# neonpixelbar.net
KiCad netlist of a schematic drawn in EAGLE
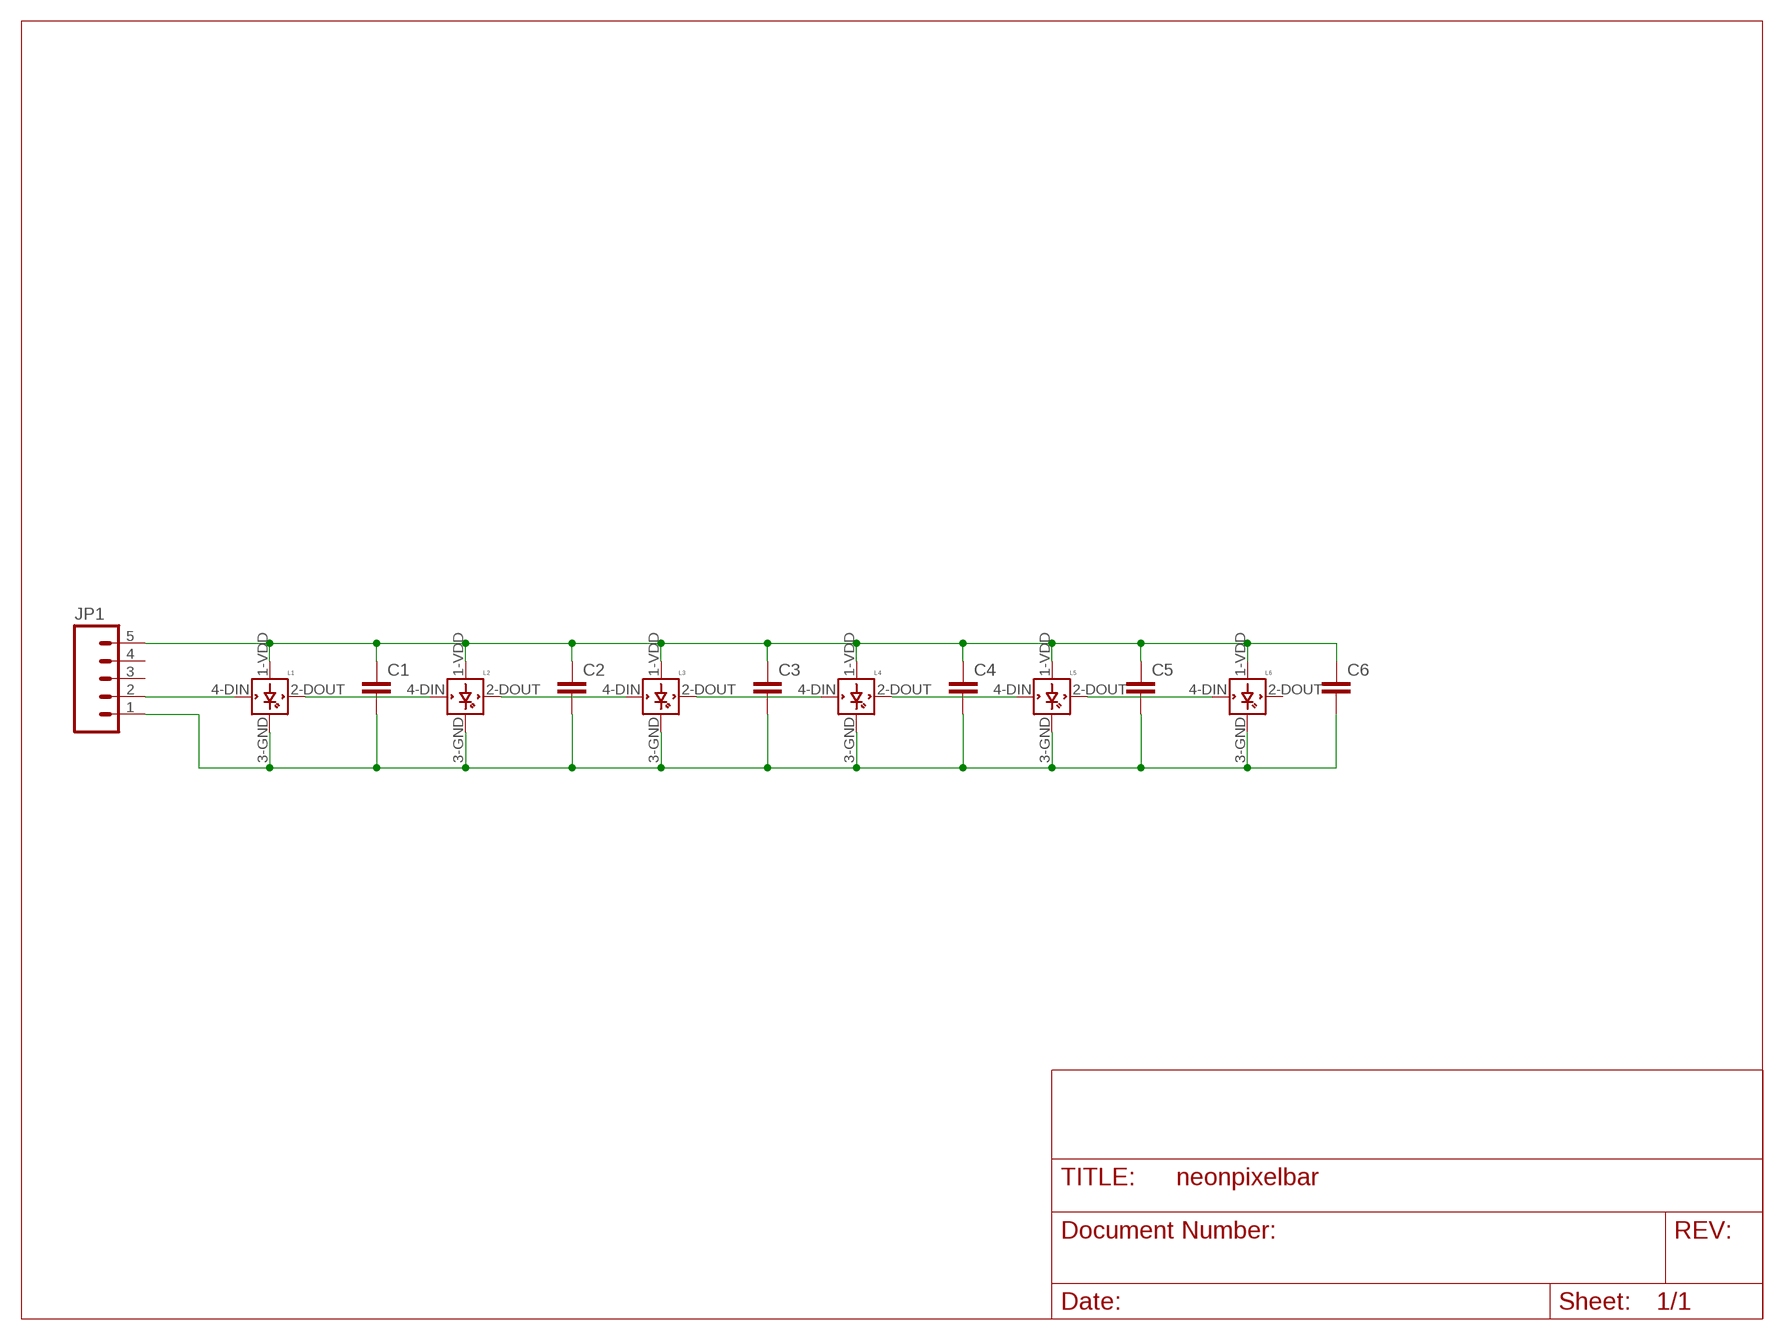
[diagram p0: schematic, sheet 1]

(export (version "E")
  (design (tool "Eeschema 10.0.6"))
  (components
    (comp (ref "C1")
      (value "CAPPTH3")
      (footprint "eagle-import:CAP-PTH-LARGE")
      (libsource (lib "eagle-import") (part "CAPPTH3"))
    )
    (comp (ref "C2")
      (value "CAPPTH3")
      (footprint "eagle-import:CAP-PTH-LARGE")
      (libsource (lib "eagle-import") (part "CAPPTH3"))
    )
    (comp (ref "C3")
      (value "CAPPTH3")
      (footprint "eagle-import:CAP-PTH-LARGE")
      (libsource (lib "eagle-import") (part "CAPPTH3"))
    )
    (comp (ref "C4")
      (value "CAPPTH3")
      (footprint "eagle-import:CAP-PTH-LARGE")
      (libsource (lib "eagle-import") (part "CAPPTH3"))
    )
    (comp (ref "C5")
      (value "CAPPTH3")
      (footprint "eagle-import:CAP-PTH-LARGE")
      (libsource (lib "eagle-import") (part "CAPPTH3"))
    )
    (comp (ref "C6")
      (value "CAPPTH3")
      (footprint "eagle-import:CAP-PTH-LARGE")
      (libsource (lib "eagle-import") (part "CAPPTH3"))
    )
    (comp (ref "JP1")
      (value "M05PTH_LONGPADS")
      (footprint "eagle-import:1X05_LONGPADS")
      (libsource (lib "eagle-import") (part "M05PTH_LONGPADS"))
    )
    (comp (ref "L1")
      (value "WS2812B")
      (footprint "eagle-import:WS2812B")
      (libsource (lib "eagle-import") (part "WS2812B"))
    )
    (comp (ref "L2")
      (value "WS2812B")
      (footprint "eagle-import:WS2812B")
      (libsource (lib "eagle-import") (part "WS2812B"))
    )
    (comp (ref "L3")
      (value "WS2812B")
      (footprint "eagle-import:WS2812B")
      (libsource (lib "eagle-import") (part "WS2812B"))
    )
    (comp (ref "L4")
      (value "WS2812B")
      (footprint "eagle-import:WS2812B")
      (libsource (lib "eagle-import") (part "WS2812B"))
    )
    (comp (ref "L5")
      (value "WS2812B")
      (footprint "eagle-import:WS2812B")
      (libsource (lib "eagle-import") (part "WS2812B"))
    )
    (comp (ref "L6")
      (value "WS2812B")
      (footprint "eagle-import:WS2812B")
      (libsource (lib "eagle-import") (part "WS2812B"))
    )
  )
  (nets
    (net (code "1") (name "Net-(L1-DIN)") (class "Default")
      (node (ref "JP1") (pin "2") (pinfunction "2_2") (pintype "passive"))
      (node (ref "L1") (pin "4-DIN") (pinfunction "DIN_4-DIN") (pintype "input"))
    )
    (net (code "2") (name "Net-(L1-DOUT)") (class "Default")
      (node (ref "L1") (pin "2-DOUT") (pinfunction "DOUT_2-DOUT") (pintype "output"))
      (node (ref "L2") (pin "4-DIN") (pinfunction "DIN_4-DIN") (pintype "input"))
    )
    (net (code "3") (name "Net-(L1-GND)") (class "Default")
      (node (ref "C1") (pin "2") (pinfunction "2_2") (pintype "passive"))
      (node (ref "C2") (pin "2") (pinfunction "2_2") (pintype "passive"))
      (node (ref "C3") (pin "2") (pinfunction "2_2") (pintype "passive"))
      (node (ref "C4") (pin "2") (pinfunction "2_2") (pintype "passive"))
      (node (ref "C5") (pin "2") (pinfunction "2_2") (pintype "passive"))
      (node (ref "C6") (pin "2") (pinfunction "2_2") (pintype "passive"))
      (node (ref "JP1") (pin "1") (pinfunction "1_1") (pintype "passive"))
      (node (ref "L1") (pin "3-GND") (pinfunction "GND_3-GND") (pintype "bidirectional"))
      (node (ref "L2") (pin "3-GND") (pinfunction "GND_3-GND") (pintype "bidirectional"))
      (node (ref "L3") (pin "3-GND") (pinfunction "GND_3-GND") (pintype "bidirectional"))
      (node (ref "L4") (pin "3-GND") (pinfunction "GND_3-GND") (pintype "bidirectional"))
      (node (ref "L5") (pin "3-GND") (pinfunction "GND_3-GND") (pintype "bidirectional"))
      (node (ref "L6") (pin "3-GND") (pinfunction "GND_3-GND") (pintype "bidirectional"))
    )
    (net (code "4") (name "Net-(L1-VDD)") (class "Default")
      (node (ref "C1") (pin "1") (pinfunction "1_1") (pintype "passive"))
      (node (ref "C2") (pin "1") (pinfunction "1_1") (pintype "passive"))
      (node (ref "C3") (pin "1") (pinfunction "1_1") (pintype "passive"))
      (node (ref "C4") (pin "1") (pinfunction "1_1") (pintype "passive"))
      (node (ref "C5") (pin "1") (pinfunction "1_1") (pintype "passive"))
      (node (ref "C6") (pin "1") (pinfunction "1_1") (pintype "passive"))
      (node (ref "JP1") (pin "5") (pinfunction "5_5") (pintype "passive"))
      (node (ref "L1") (pin "1-VDD") (pinfunction "VDD_1-VDD") (pintype "bidirectional"))
      (node (ref "L2") (pin "1-VDD") (pinfunction "VDD_1-VDD") (pintype "bidirectional"))
      (node (ref "L3") (pin "1-VDD") (pinfunction "VDD_1-VDD") (pintype "bidirectional"))
      (node (ref "L4") (pin "1-VDD") (pinfunction "VDD_1-VDD") (pintype "bidirectional"))
      (node (ref "L5") (pin "1-VDD") (pinfunction "VDD_1-VDD") (pintype "bidirectional"))
      (node (ref "L6") (pin "1-VDD") (pinfunction "VDD_1-VDD") (pintype "bidirectional"))
    )
    (net (code "5") (name "Net-(L2-DOUT)") (class "Default")
      (node (ref "L2") (pin "2-DOUT") (pinfunction "DOUT_2-DOUT") (pintype "output"))
      (node (ref "L3") (pin "4-DIN") (pinfunction "DIN_4-DIN") (pintype "input"))
    )
    (net (code "6") (name "Net-(L3-DOUT)") (class "Default")
      (node (ref "L3") (pin "2-DOUT") (pinfunction "DOUT_2-DOUT") (pintype "output"))
      (node (ref "L4") (pin "4-DIN") (pinfunction "DIN_4-DIN") (pintype "input"))
    )
    (net (code "7") (name "Net-(L4-DOUT)") (class "Default")
      (node (ref "L4") (pin "2-DOUT") (pinfunction "DOUT_2-DOUT") (pintype "output"))
      (node (ref "L5") (pin "4-DIN") (pinfunction "DIN_4-DIN") (pintype "input"))
    )
    (net (code "8") (name "Net-(L5-DOUT)") (class "Default")
      (node (ref "L5") (pin "2-DOUT") (pinfunction "DOUT_2-DOUT") (pintype "output"))
      (node (ref "L6") (pin "4-DIN") (pinfunction "DIN_4-DIN") (pintype "input"))
    )
    (net (code "9") (name "unconnected-(JP1-Pad3)") (class "Default")
      (node (ref "JP1") (pin "3") (pinfunction "3_3") (pintype "passive"))
    )
    (net (code "10") (name "unconnected-(JP1-Pad4)") (class "Default")
      (node (ref "JP1") (pin "4") (pinfunction "4_4") (pintype "passive"))
    )
    (net (code "11") (name "unconnected-(L6-DOUT-Pad2-DOUT)") (class "Default")
      (node (ref "L6") (pin "2-DOUT") (pinfunction "DOUT_2-DOUT") (pintype "output"))
    )
  )
)
